# rx.net
KiCad netlist of a schematic drawn in EAGLE
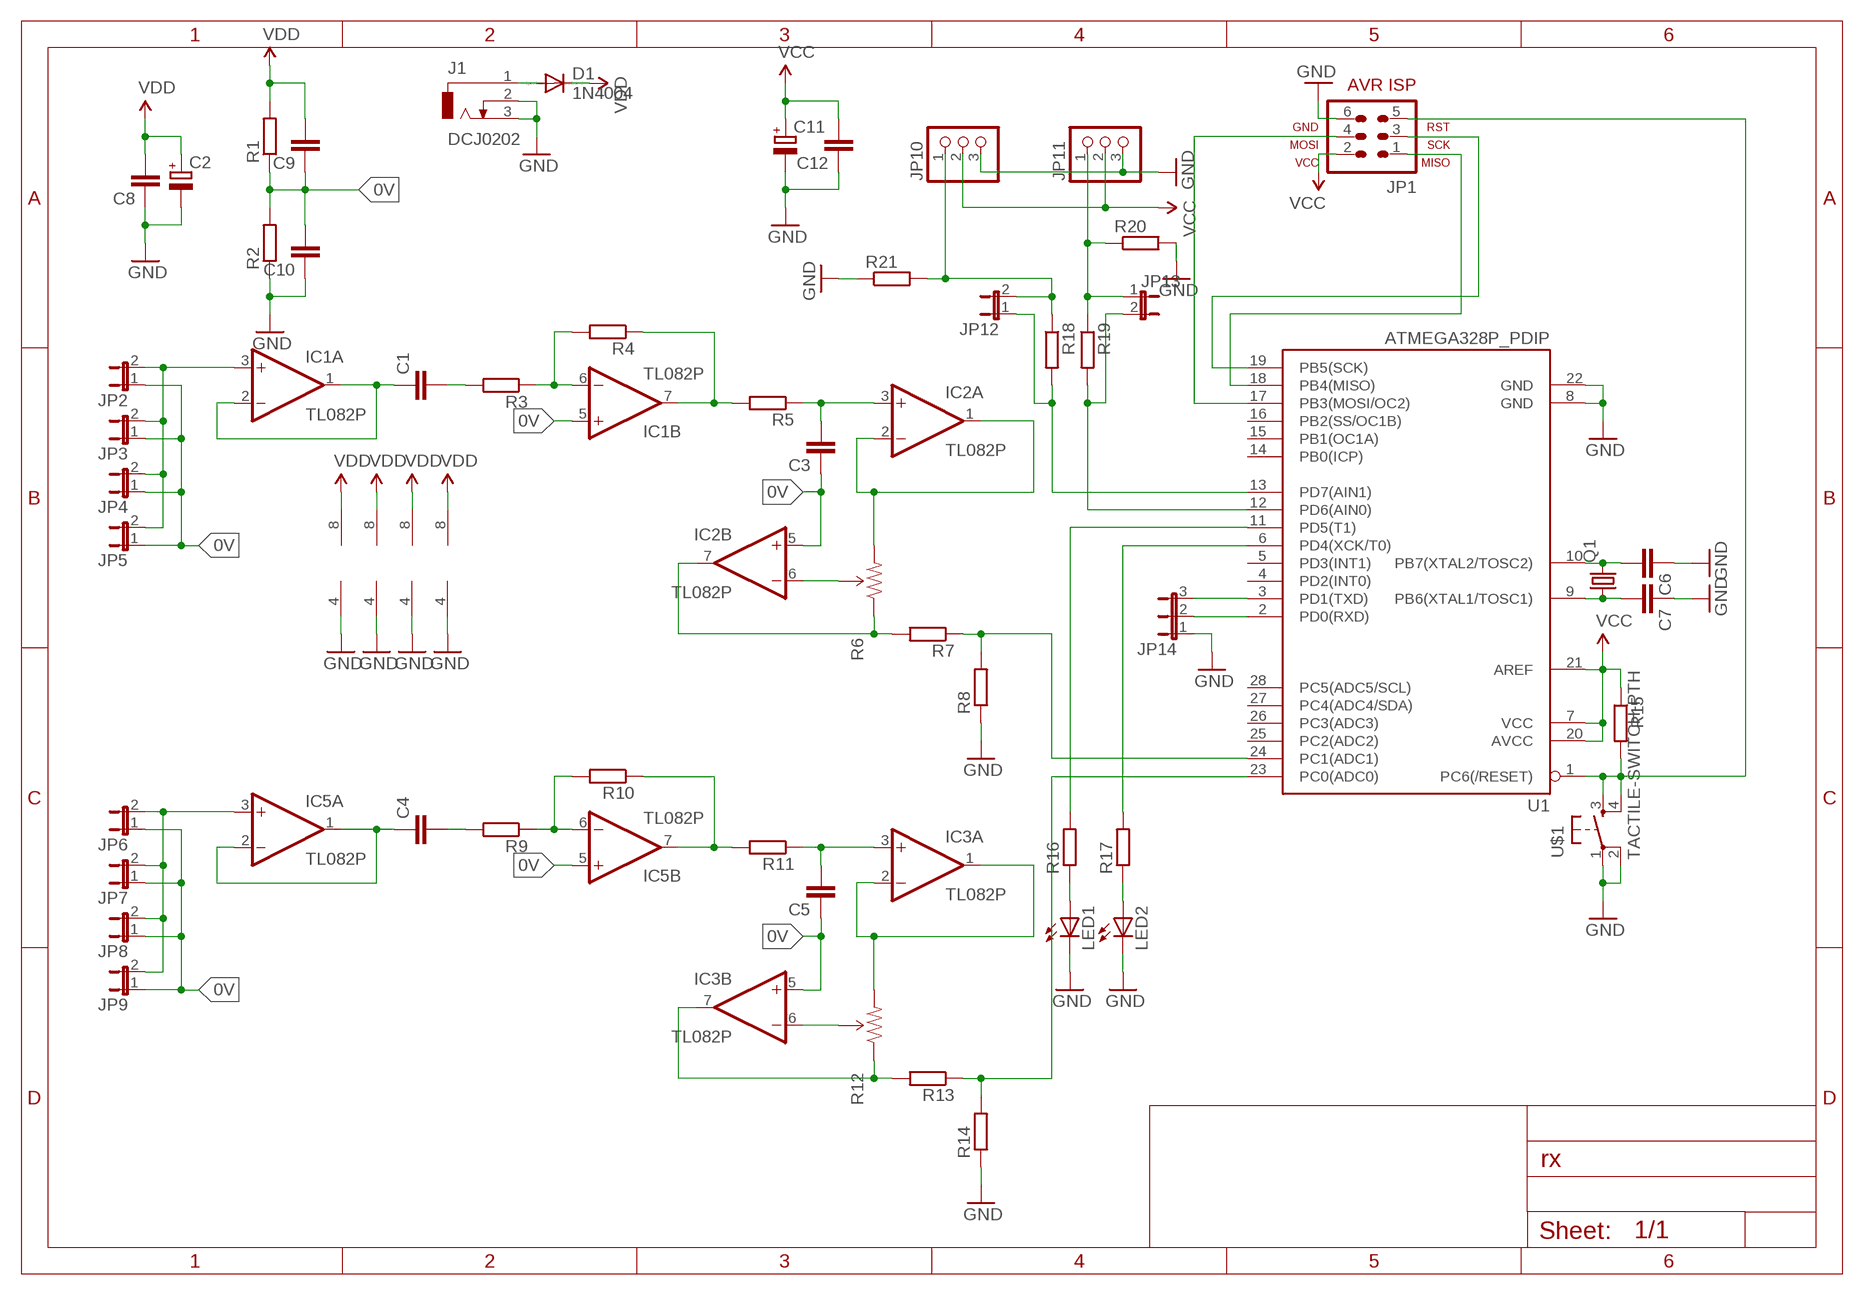
[diagram p0: schematic, sheet 1]

(export (version "E")
  (design (tool "Eeschema 10.0.6"))
  (components
    (comp (ref "C1")
      (value "C-EU050-030X075")
      (footprint "eagle-import:C050-030X075")
      (libsource (lib "eagle-import") (part "C-EU050-030X075"))
    )
    (comp (ref "C2")
      (value "CPOL-EUE5-8.5")
      (footprint "eagle-import:E5-8,5")
      (libsource (lib "eagle-import") (part "CPOL-EUE5-8.5"))
    )
    (comp (ref "C3")
      (value "C-EU050-030X075")
      (footprint "eagle-import:C050-030X075")
      (libsource (lib "eagle-import") (part "C-EU050-030X075"))
    )
    (comp (ref "C4")
      (value "C-EU050-030X075")
      (footprint "eagle-import:C050-030X075")
      (libsource (lib "eagle-import") (part "C-EU050-030X075"))
    )
    (comp (ref "C5")
      (value "C-EU050-030X075")
      (footprint "eagle-import:C050-030X075")
      (libsource (lib "eagle-import") (part "C-EU050-030X075"))
    )
    (comp (ref "C6")
      (value "C-EU050-030X075")
      (footprint "eagle-import:C050-030X075")
      (libsource (lib "eagle-import") (part "C-EU050-030X075"))
    )
    (comp (ref "C7")
      (value "C-EU050-030X075")
      (footprint "eagle-import:C050-030X075")
      (libsource (lib "eagle-import") (part "C-EU050-030X075"))
    )
    (comp (ref "C8")
      (value "C-EU050-030X075")
      (footprint "eagle-import:C050-030X075")
      (libsource (lib "eagle-import") (part "C-EU050-030X075"))
    )
    (comp (ref "C9")
      (value "C-EU050-030X075")
      (footprint "eagle-import:C050-030X075")
      (libsource (lib "eagle-import") (part "C-EU050-030X075"))
    )
    (comp (ref "C10")
      (value "C-EU050-030X075")
      (footprint "eagle-import:C050-030X075")
      (libsource (lib "eagle-import") (part "C-EU050-030X075"))
    )
    (comp (ref "C11")
      (value "CPOL-EUE5-8.5")
      (footprint "eagle-import:E5-8,5")
      (libsource (lib "eagle-import") (part "CPOL-EUE5-8.5"))
    )
    (comp (ref "C12")
      (value "C-EU050-030X075")
      (footprint "eagle-import:C050-030X075")
      (libsource (lib "eagle-import") (part "C-EU050-030X075"))
    )
    (comp (ref "D1")
      (value "1N4004")
      (footprint "eagle-import:DO41-10")
      (libsource (lib "eagle-import") (part "1N4004"))
    )
    (comp (ref "IC1")
      (value "TL082P")
      (footprint "eagle-import:DIL08")
      (libsource (lib "eagle-import") (part "TL082P"))
    )
    (comp (ref "IC2")
      (value "TL082P")
      (footprint "eagle-import:DIL08")
      (libsource (lib "eagle-import") (part "TL082P"))
    )
    (comp (ref "IC3")
      (value "TL082P")
      (footprint "eagle-import:DIL08")
      (libsource (lib "eagle-import") (part "TL082P"))
    )
    (comp (ref "IC5")
      (value "TL082P")
      (footprint "eagle-import:DIL08")
      (libsource (lib "eagle-import") (part "TL082P"))
    )
    (comp (ref "J1")
      (value "DCJ0202")
      (footprint "eagle-import:DCJ0202")
      (libsource (lib "eagle-import") (part "DCJ0202"))
    )
    (comp (ref "JP1")
      (value "AVR-ISP-6VERT")
      (footprint "eagle-import:AVR-ISP-6")
      (libsource (lib "eagle-import") (part "AVR-ISP-6VERT"))
    )
    (comp (ref "JP2")
      (value "JP1E")
      (footprint "eagle-import:JP1")
      (libsource (lib "eagle-import") (part "JP1E"))
    )
    (comp (ref "JP3")
      (value "JP1E")
      (footprint "eagle-import:JP1")
      (libsource (lib "eagle-import") (part "JP1E"))
    )
    (comp (ref "JP4")
      (value "JP1E")
      (footprint "eagle-import:JP1")
      (libsource (lib "eagle-import") (part "JP1E"))
    )
    (comp (ref "JP5")
      (value "JP1E")
      (footprint "eagle-import:JP1")
      (libsource (lib "eagle-import") (part "JP1E"))
    )
    (comp (ref "JP6")
      (value "JP1E")
      (footprint "eagle-import:JP1")
      (libsource (lib "eagle-import") (part "JP1E"))
    )
    (comp (ref "JP7")
      (value "JP1E")
      (footprint "eagle-import:JP1")
      (libsource (lib "eagle-import") (part "JP1E"))
    )
    (comp (ref "JP8")
      (value "JP1E")
      (footprint "eagle-import:JP1")
      (libsource (lib "eagle-import") (part "JP1E"))
    )
    (comp (ref "JP9")
      (value "JP1E")
      (footprint "eagle-import:JP1")
      (libsource (lib "eagle-import") (part "JP1E"))
    )
    (comp (ref "JP10")
      (value "PINHD-1X3/90")
      (footprint "eagle-import:1X03_90")
      (libsource (lib "eagle-import") (part "PINHD-1X3/90"))
    )
    (comp (ref "JP11")
      (value "PINHD-1X3/90")
      (footprint "eagle-import:1X03_90")
      (libsource (lib "eagle-import") (part "PINHD-1X3/90"))
    )
    (comp (ref "JP12")
      (value "JP1E")
      (footprint "eagle-import:JP1")
      (libsource (lib "eagle-import") (part "JP1E"))
    )
    (comp (ref "JP13")
      (value "JP1E")
      (footprint "eagle-import:JP1")
      (libsource (lib "eagle-import") (part "JP1E"))
    )
    (comp (ref "JP14")
      (value "JP2E")
      (footprint "eagle-import:JP2")
      (libsource (lib "eagle-import") (part "JP2E"))
    )
    (comp (ref "LED1")
      (value "LED5MM")
      (footprint "eagle-import:LED5MM")
      (libsource (lib "eagle-import") (part "LED5MM"))
    )
    (comp (ref "LED2")
      (value "LED5MM")
      (footprint "eagle-import:LED5MM")
      (libsource (lib "eagle-import") (part "LED5MM"))
    )
    (comp (ref "Q1")
      (value "CRYSTALHC49U70")
      (footprint "eagle-import:HC49U70")
      (libsource (lib "eagle-import") (part "CRYSTALHC49U70"))
    )
    (comp (ref "R1")
      (value "R-EU_0207/10")
      (footprint "eagle-import:0207_10")
      (libsource (lib "eagle-import") (part "R-EU_0207/10"))
    )
    (comp (ref "R2")
      (value "R-EU_0207/10")
      (footprint "eagle-import:0207_10")
      (libsource (lib "eagle-import") (part "R-EU_0207/10"))
    )
    (comp (ref "R3")
      (value "R-EU_0207/10")
      (footprint "eagle-import:0207_10")
      (libsource (lib "eagle-import") (part "R-EU_0207/10"))
    )
    (comp (ref "R4")
      (value "R-EU_0207/2V")
      (footprint "eagle-import:0207_2V")
      (libsource (lib "eagle-import") (part "R-EU_0207/2V"))
    )
    (comp (ref "R5")
      (value "R-EU_0207/2V")
      (footprint "eagle-import:0207_2V")
      (libsource (lib "eagle-import") (part "R-EU_0207/2V"))
    )
    (comp (ref "R6")
      (value "TRIMPOTPTH")
      (footprint "eagle-import:TRIM_POT_PTH")
      (libsource (lib "eagle-import") (part "TRIMPOTPTH"))
    )
    (comp (ref "R7")
      (value "R-EU_0207/10")
      (footprint "eagle-import:0207_10")
      (libsource (lib "eagle-import") (part "R-EU_0207/10"))
    )
    (comp (ref "R8")
      (value "R-EU_0207/10")
      (footprint "eagle-import:0207_10")
      (libsource (lib "eagle-import") (part "R-EU_0207/10"))
    )
    (comp (ref "R9")
      (value "R-EU_0207/10")
      (footprint "eagle-import:0207_10")
      (libsource (lib "eagle-import") (part "R-EU_0207/10"))
    )
    (comp (ref "R10")
      (value "R-EU_0207/2V")
      (footprint "eagle-import:0207_2V")
      (libsource (lib "eagle-import") (part "R-EU_0207/2V"))
    )
    (comp (ref "R11")
      (value "R-EU_0207/2V")
      (footprint "eagle-import:0207_2V")
      (libsource (lib "eagle-import") (part "R-EU_0207/2V"))
    )
    (comp (ref "R12")
      (value "TRIMPOTPTH")
      (footprint "eagle-import:TRIM_POT_PTH")
      (libsource (lib "eagle-import") (part "TRIMPOTPTH"))
    )
    (comp (ref "R13")
      (value "R-EU_0207/10")
      (footprint "eagle-import:0207_10")
      (libsource (lib "eagle-import") (part "R-EU_0207/10"))
    )
    (comp (ref "R14")
      (value "R-EU_0207/10")
      (footprint "eagle-import:0207_10")
      (libsource (lib "eagle-import") (part "R-EU_0207/10"))
    )
    (comp (ref "R15")
      (value "R-EU_0207/10")
      (footprint "eagle-import:0207_10")
      (libsource (lib "eagle-import") (part "R-EU_0207/10"))
    )
    (comp (ref "R16")
      (value "R-EU_0207/10")
      (footprint "eagle-import:0207_10")
      (libsource (lib "eagle-import") (part "R-EU_0207/10"))
    )
    (comp (ref "R17")
      (value "R-EU_0207/10")
      (footprint "eagle-import:0207_10")
      (libsource (lib "eagle-import") (part "R-EU_0207/10"))
    )
    (comp (ref "R18")
      (value "R-EU_0207/10")
      (footprint "eagle-import:0207_10")
      (libsource (lib "eagle-import") (part "R-EU_0207/10"))
    )
    (comp (ref "R19")
      (value "R-EU_0207/10")
      (footprint "eagle-import:0207_10")
      (libsource (lib "eagle-import") (part "R-EU_0207/10"))
    )
    (comp (ref "R20")
      (value "R-EU_0207/10")
      (footprint "eagle-import:0207_10")
      (libsource (lib "eagle-import") (part "R-EU_0207/10"))
    )
    (comp (ref "R21")
      (value "R-EU_0207/10")
      (footprint "eagle-import:0207_10")
      (libsource (lib "eagle-import") (part "R-EU_0207/10"))
    )
    (comp (ref "U$1")
      (value "TACTILE-SWITCH-PTH")
      (footprint "eagle-import:TAC-SWITCH-PTH")
      (libsource (lib "eagle-import") (part "TACTILE-SWITCH-PTH"))
    )
    (comp (ref "U1")
      (value "ATMEGA328P_PDIP")
      (footprint "eagle-import:DIL28-3")
      (libsource (lib "eagle-import") (part "ATMEGA328P_PDIP"))
    )
  )
  (nets
    (net (code "1") (name "0V") (class "Default")
      (node (ref "C10") (pin "2") (pinfunction "2_2") (pintype "passive"))
      (node (ref "C3") (pin "1") (pinfunction "1_1") (pintype "passive"))
      (node (ref "C5") (pin "1") (pinfunction "1_1") (pintype "passive"))
      (node (ref "C9") (pin "1") (pinfunction "1_1") (pintype "passive"))
      (node (ref "IC1") (pin "5") (pinfunction "+IN_5") (pintype "input"))
      (node (ref "IC2") (pin "5") (pinfunction "+IN_5") (pintype "input"))
      (node (ref "IC3") (pin "5") (pinfunction "+IN_5") (pintype "input"))
      (node (ref "IC5") (pin "5") (pinfunction "+IN_5") (pintype "input"))
      (node (ref "JP2") (pin "1") (pinfunction "1_1") (pintype "passive"))
      (node (ref "JP3") (pin "1") (pinfunction "1_1") (pintype "passive"))
      (node (ref "JP4") (pin "1") (pinfunction "1_1") (pintype "passive"))
      (node (ref "JP5") (pin "1") (pinfunction "1_1") (pintype "passive"))
      (node (ref "JP6") (pin "1") (pinfunction "1_1") (pintype "passive"))
      (node (ref "JP7") (pin "1") (pinfunction "1_1") (pintype "passive"))
      (node (ref "JP8") (pin "1") (pinfunction "1_1") (pintype "passive"))
      (node (ref "JP9") (pin "1") (pinfunction "1_1") (pintype "passive"))
      (node (ref "R1") (pin "1") (pinfunction "1_1") (pintype "passive"))
      (node (ref "R2") (pin "2") (pinfunction "2_2") (pintype "passive"))
    )
    (net (code "2") (name "GND") (class "Default")
      (node (ref "C10") (pin "1") (pinfunction "1_1") (pintype "passive"))
      (node (ref "C11") (pin "-") (pinfunction "-_-") (pintype "passive"))
      (node (ref "C12") (pin "1") (pinfunction "1_1") (pintype "passive"))
      (node (ref "C2") (pin "-") (pinfunction "-_-") (pintype "passive"))
      (node (ref "C6") (pin "1") (pinfunction "1_1") (pintype "passive"))
      (node (ref "C7") (pin "1") (pinfunction "1_1") (pintype "passive"))
      (node (ref "C8") (pin "1") (pinfunction "1_1") (pintype "passive"))
      (node (ref "IC1") (pin "4") (pinfunction "V-_4") (pintype "power_in"))
      (node (ref "IC2") (pin "4") (pinfunction "V-_4") (pintype "power_in"))
      (node (ref "IC3") (pin "4") (pinfunction "V-_4") (pintype "power_in"))
      (node (ref "IC5") (pin "4") (pinfunction "V-_4") (pintype "power_in"))
      (node (ref "J1") (pin "2") (pinfunction "2_2") (pintype "passive"))
      (node (ref "J1") (pin "3") (pinfunction "3_3") (pintype "passive"))
      (node (ref "JP1") (pin "6") (pinfunction "6_6") (pintype "passive"))
      (node (ref "JP10") (pin "3") (pinfunction "3_3") (pintype "passive"))
      (node (ref "JP11") (pin "3") (pinfunction "3_3") (pintype "passive"))
      (node (ref "JP14") (pin "1") (pinfunction "1_1") (pintype "passive"))
      (node (ref "LED1") (pin "K") (pinfunction "C_K") (pintype "passive"))
      (node (ref "LED2") (pin "K") (pinfunction "C_K") (pintype "passive"))
      (node (ref "R14") (pin "1") (pinfunction "1_1") (pintype "passive"))
      (node (ref "R2") (pin "1") (pinfunction "1_1") (pintype "passive"))
      (node (ref "R20") (pin "2") (pinfunction "2_2") (pintype "passive"))
      (node (ref "R21") (pin "1") (pinfunction "1_1") (pintype "passive"))
      (node (ref "R8") (pin "1") (pinfunction "1_1") (pintype "passive"))
      (node (ref "U$1") (pin "1") (pinfunction "1_1") (pintype "passive"))
      (node (ref "U$1") (pin "2") (pinfunction "2_2") (pintype "passive"))
      (node (ref "U1") (pin "22") (pinfunction "GND_22") (pintype "bidirectional"))
      (node (ref "U1") (pin "8") (pinfunction "GND_8") (pintype "bidirectional"))
    )
    (net (code "3") (name "Net-(C1-Pad2)") (class "Default")
      (node (ref "C1") (pin "2") (pinfunction "2_2") (pintype "passive"))
      (node (ref "R3") (pin "2") (pinfunction "2_2") (pintype "passive"))
    )
    (net (code "4") (name "Net-(C4-Pad2)") (class "Default")
      (node (ref "C4") (pin "2") (pinfunction "2_2") (pintype "passive"))
      (node (ref "R9") (pin "2") (pinfunction "2_2") (pintype "passive"))
    )
    (net (code "5") (name "Net-(D1-PadA)") (class "Default")
      (node (ref "D1") (pin "A") (pinfunction "A_A") (pintype "passive"))
      (node (ref "J1") (pin "1") (pinfunction "1_1") (pintype "passive"))
    )
    (net (code "6") (name "Net-(IC1A-+IN)") (class "Default")
      (node (ref "IC1") (pin "3") (pinfunction "+IN_3") (pintype "input"))
      (node (ref "JP2") (pin "2") (pinfunction "2_2") (pintype "passive"))
      (node (ref "JP3") (pin "2") (pinfunction "2_2") (pintype "passive"))
      (node (ref "JP4") (pin "2") (pinfunction "2_2") (pintype "passive"))
      (node (ref "JP5") (pin "2") (pinfunction "2_2") (pintype "passive"))
    )
    (net (code "7") (name "Net-(IC1A--IN)") (class "Default")
      (node (ref "C1") (pin "1") (pinfunction "1_1") (pintype "passive"))
      (node (ref "IC1") (pin "1") (pinfunction "OUT_1") (pintype "output"))
      (node (ref "IC1") (pin "2") (pinfunction "-IN_2") (pintype "input"))
    )
    (net (code "8") (name "Net-(IC1B--IN)") (class "Default")
      (node (ref "IC1") (pin "6") (pinfunction "-IN_6") (pintype "input"))
      (node (ref "R3") (pin "1") (pinfunction "1_1") (pintype "passive"))
      (node (ref "R4") (pin "2") (pinfunction "2_2") (pintype "passive"))
    )
    (net (code "9") (name "Net-(IC1B-OUT)") (class "Default")
      (node (ref "IC1") (pin "7") (pinfunction "OUT_7") (pintype "output"))
      (node (ref "R4") (pin "1") (pinfunction "1_1") (pintype "passive"))
      (node (ref "R5") (pin "2") (pinfunction "2_2") (pintype "passive"))
    )
    (net (code "10") (name "Net-(IC2A-+IN)") (class "Default")
      (node (ref "C3") (pin "2") (pinfunction "2_2") (pintype "passive"))
      (node (ref "IC2") (pin "3") (pinfunction "+IN_3") (pintype "input"))
      (node (ref "R5") (pin "1") (pinfunction "1_1") (pintype "passive"))
    )
    (net (code "11") (name "Net-(IC2A--IN)") (class "Default")
      (node (ref "IC2") (pin "1") (pinfunction "OUT_1") (pintype "output"))
      (node (ref "IC2") (pin "2") (pinfunction "-IN_2") (pintype "input"))
      (node (ref "R6") (pin "3") (pinfunction "CW_3") (pintype "passive"))
    )
    (net (code "12") (name "Net-(IC2B--IN)") (class "Default")
      (node (ref "IC2") (pin "6") (pinfunction "-IN_6") (pintype "input"))
      (node (ref "R6") (pin "2") (pinfunction "WIPER_2") (pintype "passive"))
    )
    (net (code "13") (name "Net-(IC2B-OUT)") (class "Default")
      (node (ref "IC2") (pin "7") (pinfunction "OUT_7") (pintype "output"))
      (node (ref "R6") (pin "1") (pinfunction "CCW_1") (pintype "passive"))
      (node (ref "R7") (pin "2") (pinfunction "2_2") (pintype "passive"))
    )
    (net (code "14") (name "Net-(IC3A-+IN)") (class "Default")
      (node (ref "C5") (pin "2") (pinfunction "2_2") (pintype "passive"))
      (node (ref "IC3") (pin "3") (pinfunction "+IN_3") (pintype "input"))
      (node (ref "R11") (pin "1") (pinfunction "1_1") (pintype "passive"))
    )
    (net (code "15") (name "Net-(IC3A--IN)") (class "Default")
      (node (ref "IC3") (pin "1") (pinfunction "OUT_1") (pintype "output"))
      (node (ref "IC3") (pin "2") (pinfunction "-IN_2") (pintype "input"))
      (node (ref "R12") (pin "3") (pinfunction "CW_3") (pintype "passive"))
    )
    (net (code "16") (name "Net-(IC3B--IN)") (class "Default")
      (node (ref "IC3") (pin "6") (pinfunction "-IN_6") (pintype "input"))
      (node (ref "R12") (pin "2") (pinfunction "WIPER_2") (pintype "passive"))
    )
    (net (code "17") (name "Net-(IC3B-OUT)") (class "Default")
      (node (ref "IC3") (pin "7") (pinfunction "OUT_7") (pintype "output"))
      (node (ref "R12") (pin "1") (pinfunction "CCW_1") (pintype "passive"))
      (node (ref "R13") (pin "2") (pinfunction "2_2") (pintype "passive"))
    )
    (net (code "18") (name "Net-(IC5A-+IN)") (class "Default")
      (node (ref "IC5") (pin "3") (pinfunction "+IN_3") (pintype "input"))
      (node (ref "JP6") (pin "2") (pinfunction "2_2") (pintype "passive"))
      (node (ref "JP7") (pin "2") (pinfunction "2_2") (pintype "passive"))
      (node (ref "JP8") (pin "2") (pinfunction "2_2") (pintype "passive"))
      (node (ref "JP9") (pin "2") (pinfunction "2_2") (pintype "passive"))
    )
    (net (code "19") (name "Net-(IC5A--IN)") (class "Default")
      (node (ref "C4") (pin "1") (pinfunction "1_1") (pintype "passive"))
      (node (ref "IC5") (pin "1") (pinfunction "OUT_1") (pintype "output"))
      (node (ref "IC5") (pin "2") (pinfunction "-IN_2") (pintype "input"))
    )
    (net (code "20") (name "Net-(IC5B--IN)") (class "Default")
      (node (ref "IC5") (pin "6") (pinfunction "-IN_6") (pintype "input"))
      (node (ref "R10") (pin "2") (pinfunction "2_2") (pintype "passive"))
      (node (ref "R9") (pin "1") (pinfunction "1_1") (pintype "passive"))
    )
    (net (code "21") (name "Net-(IC5B-OUT)") (class "Default")
      (node (ref "IC5") (pin "7") (pinfunction "OUT_7") (pintype "output"))
      (node (ref "R10") (pin "1") (pinfunction "1_1") (pintype "passive"))
      (node (ref "R11") (pin "2") (pinfunction "2_2") (pintype "passive"))
    )
    (net (code "22") (name "Net-(JP10-Pad1)") (class "Default")
      (node (ref "JP10") (pin "1") (pinfunction "1_1") (pintype "passive"))
      (node (ref "JP12") (pin "2") (pinfunction "2_2") (pintype "passive"))
      (node (ref "R18") (pin "1") (pinfunction "1_1") (pintype "passive"))
      (node (ref "R21") (pin "2") (pinfunction "2_2") (pintype "passive"))
    )
    (net (code "23") (name "Net-(JP11-Pad1)") (class "Default")
      (node (ref "JP11") (pin "1") (pinfunction "1_1") (pintype "passive"))
      (node (ref "JP13") (pin "1") (pinfunction "1_1") (pintype "passive"))
      (node (ref "R19") (pin "1") (pinfunction "1_1") (pintype "passive"))
      (node (ref "R20") (pin "1") (pinfunction "1_1") (pintype "passive"))
    )
    (net (code "24") (name "Net-(LED1-PadA)") (class "Default")
      (node (ref "LED1") (pin "A") (pinfunction "A_A") (pintype "passive"))
      (node (ref "R16") (pin "1") (pinfunction "1_1") (pintype "passive"))
    )
    (net (code "25") (name "Net-(LED2-PadA)") (class "Default")
      (node (ref "LED2") (pin "A") (pinfunction "A_A") (pintype "passive"))
      (node (ref "R17") (pin "1") (pinfunction "1_1") (pintype "passive"))
    )
    (net (code "26") (name "Net-(U1-PB3(MOSI{slash}OC2))") (class "Default")
      (node (ref "JP1") (pin "4") (pinfunction "4_4") (pintype "passive"))
      (node (ref "U1") (pin "17") (pinfunction "PB3(MOSI/OC2)_17") (pintype "bidirectional"))
    )
    (net (code "27") (name "Net-(U1-PB4(MISO))") (class "Default")
      (node (ref "JP1") (pin "1") (pinfunction "1_1") (pintype "passive"))
      (node (ref "U1") (pin "18") (pinfunction "PB4(MISO)_18") (pintype "bidirectional"))
    )
    (net (code "28") (name "Net-(U1-PB5(SCK))") (class "Default")
      (node (ref "JP1") (pin "3") (pinfunction "3_3") (pintype "passive"))
      (node (ref "U1") (pin "19") (pinfunction "PB5(SCK)_19") (pintype "bidirectional"))
    )
    (net (code "29") (name "Net-(U1-PB6(XTAL1{slash}TOSC1))") (class "Default")
      (node (ref "C7") (pin "2") (pinfunction "2_2") (pintype "passive"))
      (node (ref "Q1") (pin "1") (pinfunction "1_1") (pintype "passive"))
      (node (ref "U1") (pin "9") (pinfunction "PB6(XTAL1/TOSC1)_9") (pintype "bidirectional"))
    )
    (net (code "30") (name "Net-(U1-PB7(XTAL2{slash}TOSC2))") (class "Default")
      (node (ref "C6") (pin "2") (pinfunction "2_2") (pintype "passive"))
      (node (ref "Q1") (pin "2") (pinfunction "2_2") (pintype "passive"))
      (node (ref "U1") (pin "10") (pinfunction "PB7(XTAL2/TOSC2)_10") (pintype "bidirectional"))
    )
    (net (code "31") (name "Net-(U1-PC0(ADC0))") (class "Default")
      (node (ref "R13") (pin "1") (pinfunction "1_1") (pintype "passive"))
      (node (ref "R14") (pin "2") (pinfunction "2_2") (pintype "passive"))
      (node (ref "U1") (pin "23") (pinfunction "PC0(ADC0)_23") (pintype "bidirectional"))
    )
    (net (code "32") (name "Net-(U1-PC1(ADC1))") (class "Default")
      (node (ref "R7") (pin "1") (pinfunction "1_1") (pintype "passive"))
      (node (ref "R8") (pin "2") (pinfunction "2_2") (pintype "passive"))
      (node (ref "U1") (pin "24") (pinfunction "PC1(ADC1)_24") (pintype "bidirectional"))
    )
    (net (code "33") (name "Net-(U1-PC6({slash}RESET))") (class "Default")
      (node (ref "JP1") (pin "5") (pinfunction "5_5") (pintype "passive"))
      (node (ref "R15") (pin "2") (pinfunction "2_2") (pintype "passive"))
      (node (ref "U$1") (pin "3") (pinfunction "3_3") (pintype "passive"))
      (node (ref "U$1") (pin "4") (pinfunction "4_4") (pintype "passive"))
      (node (ref "U1") (pin "1") (pinfunction "PC6(/RESET)_1") (pintype "bidirectional"))
    )
    (net (code "34") (name "Net-(U1-PD0(RXD))") (class "Default")
      (node (ref "JP14") (pin "2") (pinfunction "2_2") (pintype "passive"))
      (node (ref "U1") (pin "2") (pinfunction "PD0(RXD)_2") (pintype "bidirectional"))
    )
    (net (code "35") (name "Net-(U1-PD1(TXD))") (class "Default")
      (node (ref "JP14") (pin "3") (pinfunction "3_3") (pintype "passive"))
      (node (ref "U1") (pin "3") (pinfunction "PD1(TXD)_3") (pintype "bidirectional"))
    )
    (net (code "36") (name "Net-(U1-PD4(XCK{slash}T0))") (class "Default")
      (node (ref "R17") (pin "2") (pinfunction "2_2") (pintype "passive"))
      (node (ref "U1") (pin "6") (pinfunction "PD4(XCK/T0)_6") (pintype "bidirectional"))
    )
    (net (code "37") (name "Net-(U1-PD5(T1))") (class "Default")
      (node (ref "R16") (pin "2") (pinfunction "2_2") (pintype "passive"))
      (node (ref "U1") (pin "11") (pinfunction "PD5(T1)_11") (pintype "bidirectional"))
    )
    (net (code "38") (name "Net-(U1-PD6(AIN0))") (class "Default")
      (node (ref "JP13") (pin "2") (pinfunction "2_2") (pintype "passive"))
      (node (ref "R19") (pin "2") (pinfunction "2_2") (pintype "passive"))
      (node (ref "U1") (pin "12") (pinfunction "PD6(AIN0)_12") (pintype "bidirectional"))
    )
    (net (code "39") (name "Net-(U1-PD7(AIN1))") (class "Default")
      (node (ref "JP12") (pin "1") (pinfunction "1_1") (pintype "passive"))
      (node (ref "R18") (pin "2") (pinfunction "2_2") (pintype "passive"))
      (node (ref "U1") (pin "13") (pinfunction "PD7(AIN1)_13") (pintype "bidirectional"))
    )
    (net (code "40") (name "VCC") (class "Default")
      (node (ref "C11") (pin "+") (pinfunction "+_+") (pintype "passive"))
      (node (ref "C12") (pin "2") (pinfunction "2_2") (pintype "passive"))
      (node (ref "JP1") (pin "2") (pinfunction "2_2") (pintype "passive"))
      (node (ref "JP10") (pin "2") (pinfunction "2_2") (pintype "passive"))
      (node (ref "JP11") (pin "2") (pinfunction "2_2") (pintype "passive"))
      (node (ref "R15") (pin "1") (pinfunction "1_1") (pintype "passive"))
      (node (ref "U1") (pin "20") (pinfunction "AVCC_20") (pintype "bidirectional"))
      (node (ref "U1") (pin "21") (pinfunction "AREF_21") (pintype "bidirectional"))
      (node (ref "U1") (pin "7") (pinfunction "VCC_7") (pintype "bidirectional"))
    )
    (net (code "41") (name "VDD") (class "Default")
      (node (ref "C2") (pin "+") (pinfunction "+_+") (pintype "passive"))
      (node (ref "C8") (pin "2") (pinfunction "2_2") (pintype "passive"))
      (node (ref "C9") (pin "2") (pinfunction "2_2") (pintype "passive"))
      (node (ref "D1") (pin "C") (pinfunction "C_C") (pintype "passive"))
      (node (ref "IC1") (pin "8") (pinfunction "V+_8") (pintype "power_in"))
      (node (ref "IC2") (pin "8") (pinfunction "V+_8") (pintype "power_in"))
      (node (ref "IC3") (pin "8") (pinfunction "V+_8") (pintype "power_in"))
      (node (ref "IC5") (pin "8") (pinfunction "V+_8") (pintype "power_in"))
      (node (ref "R1") (pin "2") (pinfunction "2_2") (pintype "passive"))
    )
    (net (code "42") (name "unconnected-(U1-PB0(ICP)-Pad14)") (class "Default")
      (node (ref "U1") (pin "14") (pinfunction "PB0(ICP)_14") (pintype "bidirectional"))
    )
    (net (code "43") (name "unconnected-(U1-PB1(OC1A)-Pad15)") (class "Default")
      (node (ref "U1") (pin "15") (pinfunction "PB1(OC1A)_15") (pintype "bidirectional"))
    )
    (net (code "44") (name "unconnected-(U1-PB2(SS{slash}OC1B)-Pad16)") (class "Default")
      (node (ref "U1") (pin "16") (pinfunction "PB2(SS/OC1B)_16") (pintype "bidirectional"))
    )
    (net (code "45") (name "unconnected-(U1-PC2(ADC2)-Pad25)") (class "Default")
      (node (ref "U1") (pin "25") (pinfunction "PC2(ADC2)_25") (pintype "bidirectional"))
    )
    (net (code "46") (name "unconnected-(U1-PC3(ADC3)-Pad26)") (class "Default")
      (node (ref "U1") (pin "26") (pinfunction "PC3(ADC3)_26") (pintype "bidirectional"))
    )
    (net (code "47") (name "unconnected-(U1-PC4(ADC4{slash}SDA)-Pad27)") (class "Default")
      (node (ref "U1") (pin "27") (pinfunction "PC4(ADC4/SDA)_27") (pintype "bidirectional"))
    )
    (net (code "48") (name "unconnected-(U1-PC5(ADC5{slash}SCL)-Pad28)") (class "Default")
      (node (ref "U1") (pin "28") (pinfunction "PC5(ADC5/SCL)_28") (pintype "bidirectional"))
    )
    (net (code "49") (name "unconnected-(U1-PD2(INT0)-Pad4)") (class "Default")
      (node (ref "U1") (pin "4") (pinfunction "PD2(INT0)_4") (pintype "bidirectional"))
    )
    (net (code "50") (name "unconnected-(U1-PD3(INT1)-Pad5)") (class "Default")
      (node (ref "U1") (pin "5") (pinfunction "PD3(INT1)_5") (pintype "bidirectional"))
    )
  )
)
